# mcu.net
KiCad netlist of a schematic drawn in Altium Designer
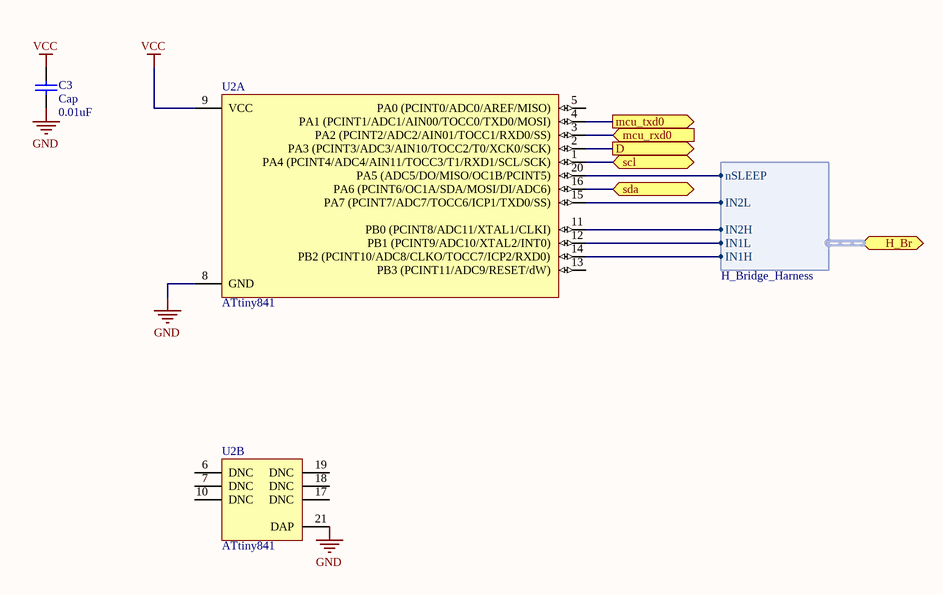
[diagram p0: mcu.SchDoc]

(export (version "E")
  (design (tool "Eeschema 10.0.6"))
  (components
    (comp (ref "C3")
      (value "Cap")
      (footprint "RAD-0.3")
      (description "Capacitor")
      (fields (field (name "ALTIUM_VALUE") "0.01uF") (field (name "PUBLISHER") "Altium Limited"))
      (libsource (lib "Miscellaneous Devices") (part "Cap"))
    )
    (comp (ref "U2")
      (value "ATtiny841")
      (footprint "20M1_L")
      (description "8-bit AVR Microcontroller with 4/8K Bytes In-System  Programmable Flash")
      (libsource (lib "motee_v2") (part "ATtiny841"))
    )
  )
  (nets
    (net (code "2") (name "/D") (class "Default")
      (node (ref "U2") (pin "2") (pinfunction "PA3_(PCINT3/ADC3/AIN10/TOCC2/T0/XCK0/SCK)_2") (pintype "bidirectional"))
    )
    (net (code "3") (name "/IN1H") (class "Default")
      (node (ref "U2") (pin "14") (pinfunction "PB2_(PCINT10/ADC8/CLKO/TOCC7/ICP2/RXD0)_14") (pintype "bidirectional"))
    )
    (net (code "4") (name "/IN1L") (class "Default")
      (node (ref "U2") (pin "12") (pinfunction "PB1_(PCINT9/ADC10/XTAL2/INT0)_12") (pintype "bidirectional"))
    )
    (net (code "5") (name "/IN2H") (class "Default")
      (node (ref "U2") (pin "11") (pinfunction "PB0_(PCINT8/ADC11/XTAL1/CLKI)_11") (pintype "bidirectional"))
    )
    (net (code "6") (name "/IN2L") (class "Default")
      (node (ref "U2") (pin "15") (pinfunction "PA7_(PCINT7/ADC7/TOCC6/ICP1/TXD0/SS)_15") (pintype "bidirectional"))
    )
    (net (code "7") (name "/mcu_rxd0") (class "Default")
      (node (ref "U2") (pin "3") (pinfunction "PA2_(PCINT2/ADC2/AIN01/TOCC1/RXD0/SS)_3") (pintype "bidirectional"))
    )
    (net (code "8") (name "/mcu_txd0") (class "Default")
      (node (ref "U2") (pin "4") (pinfunction "PA1_(PCINT1/ADC1/AIN00/TOCC0/TXD0/MOSI)_4") (pintype "bidirectional"))
    )
    (net (code "9") (name "/nSLEEP") (class "Default")
      (node (ref "U2") (pin "20") (pinfunction "PA5_(ADC5/DO/MISO/OC1B/PCINT5)_20") (pintype "bidirectional"))
    )
    (net (code "10") (name "/scl") (class "Default")
      (node (ref "U2") (pin "1") (pinfunction "PA4_(PCINT4/ADC4/AIN11/TOCC3/T1/RXD1/SCL/SCK)_1") (pintype "bidirectional"))
    )
    (net (code "11") (name "/sda") (class "Default")
      (node (ref "U2") (pin "16") (pinfunction "PA6_(PCINT6/OC1A/SDA/MOSI/DI/ADC6)_16") (pintype "bidirectional"))
    )
    (net (code "13") (name "GND") (class "Default")
      (node (ref "C3") (pin "1") (pinfunction "1_1") (pintype "passive"))
      (node (ref "U2") (pin "21") (pinfunction "DAP_21") (pintype "power_in"))
      (node (ref "U2") (pin "8") (pinfunction "GND_8") (pintype "power_in"))
    )
    (net (code "14") (name "VCC") (class "Default")
      (node (ref "C3") (pin "2") (pinfunction "2_2") (pintype "passive"))
      (node (ref "U2") (pin "9") (pinfunction "VCC_9") (pintype "power_in"))
    )
    (net (code "15") (name "unconnected-(U2A-PA0_(PCINT0{slash}ADC0{slash}AREF{slash}MISO)-Pad5)") (class "Default")
      (node (ref "U2") (pin "5") (pinfunction "PA0_(PCINT0/ADC0/AREF/MISO)_5") (pintype "bidirectional"))
    )
    (net (code "16") (name "unconnected-(U2A-PB3_(PCINT11{slash}ADC9{slash}RESET{slash}dW)-Pad13)") (class "Default")
      (node (ref "U2") (pin "13") (pinfunction "PB3_(PCINT11/ADC9/RESET/dW)_13") (pintype "bidirectional"))
    )
    (net (code "17") (name "unconnected-(U2B-DNC-Pad6)") (class "Default")
      (node (ref "U2") (pin "6") (pinfunction "DNC_6") (pintype "passive"))
    )
    (net (code "18") (name "unconnected-(U2B-DNC-Pad7)") (class "Default")
      (node (ref "U2") (pin "7") (pinfunction "DNC_7") (pintype "passive"))
    )
    (net (code "19") (name "unconnected-(U2B-DNC-Pad10)") (class "Default")
      (node (ref "U2") (pin "10") (pinfunction "DNC_10") (pintype "passive"))
    )
    (net (code "20") (name "unconnected-(U2B-DNC-Pad17)") (class "Default")
      (node (ref "U2") (pin "17") (pinfunction "DNC_17") (pintype "passive"))
    )
    (net (code "21") (name "unconnected-(U2B-DNC-Pad18)") (class "Default")
      (node (ref "U2") (pin "18") (pinfunction "DNC_18") (pintype "passive"))
    )
    (net (code "22") (name "unconnected-(U2B-DNC-Pad19)") (class "Default")
      (node (ref "U2") (pin "19") (pinfunction "DNC_19") (pintype "passive"))
    )
  )
)
